# ridicideskaV3.net
KiCad netlist of a schematic drawn in EAGLE
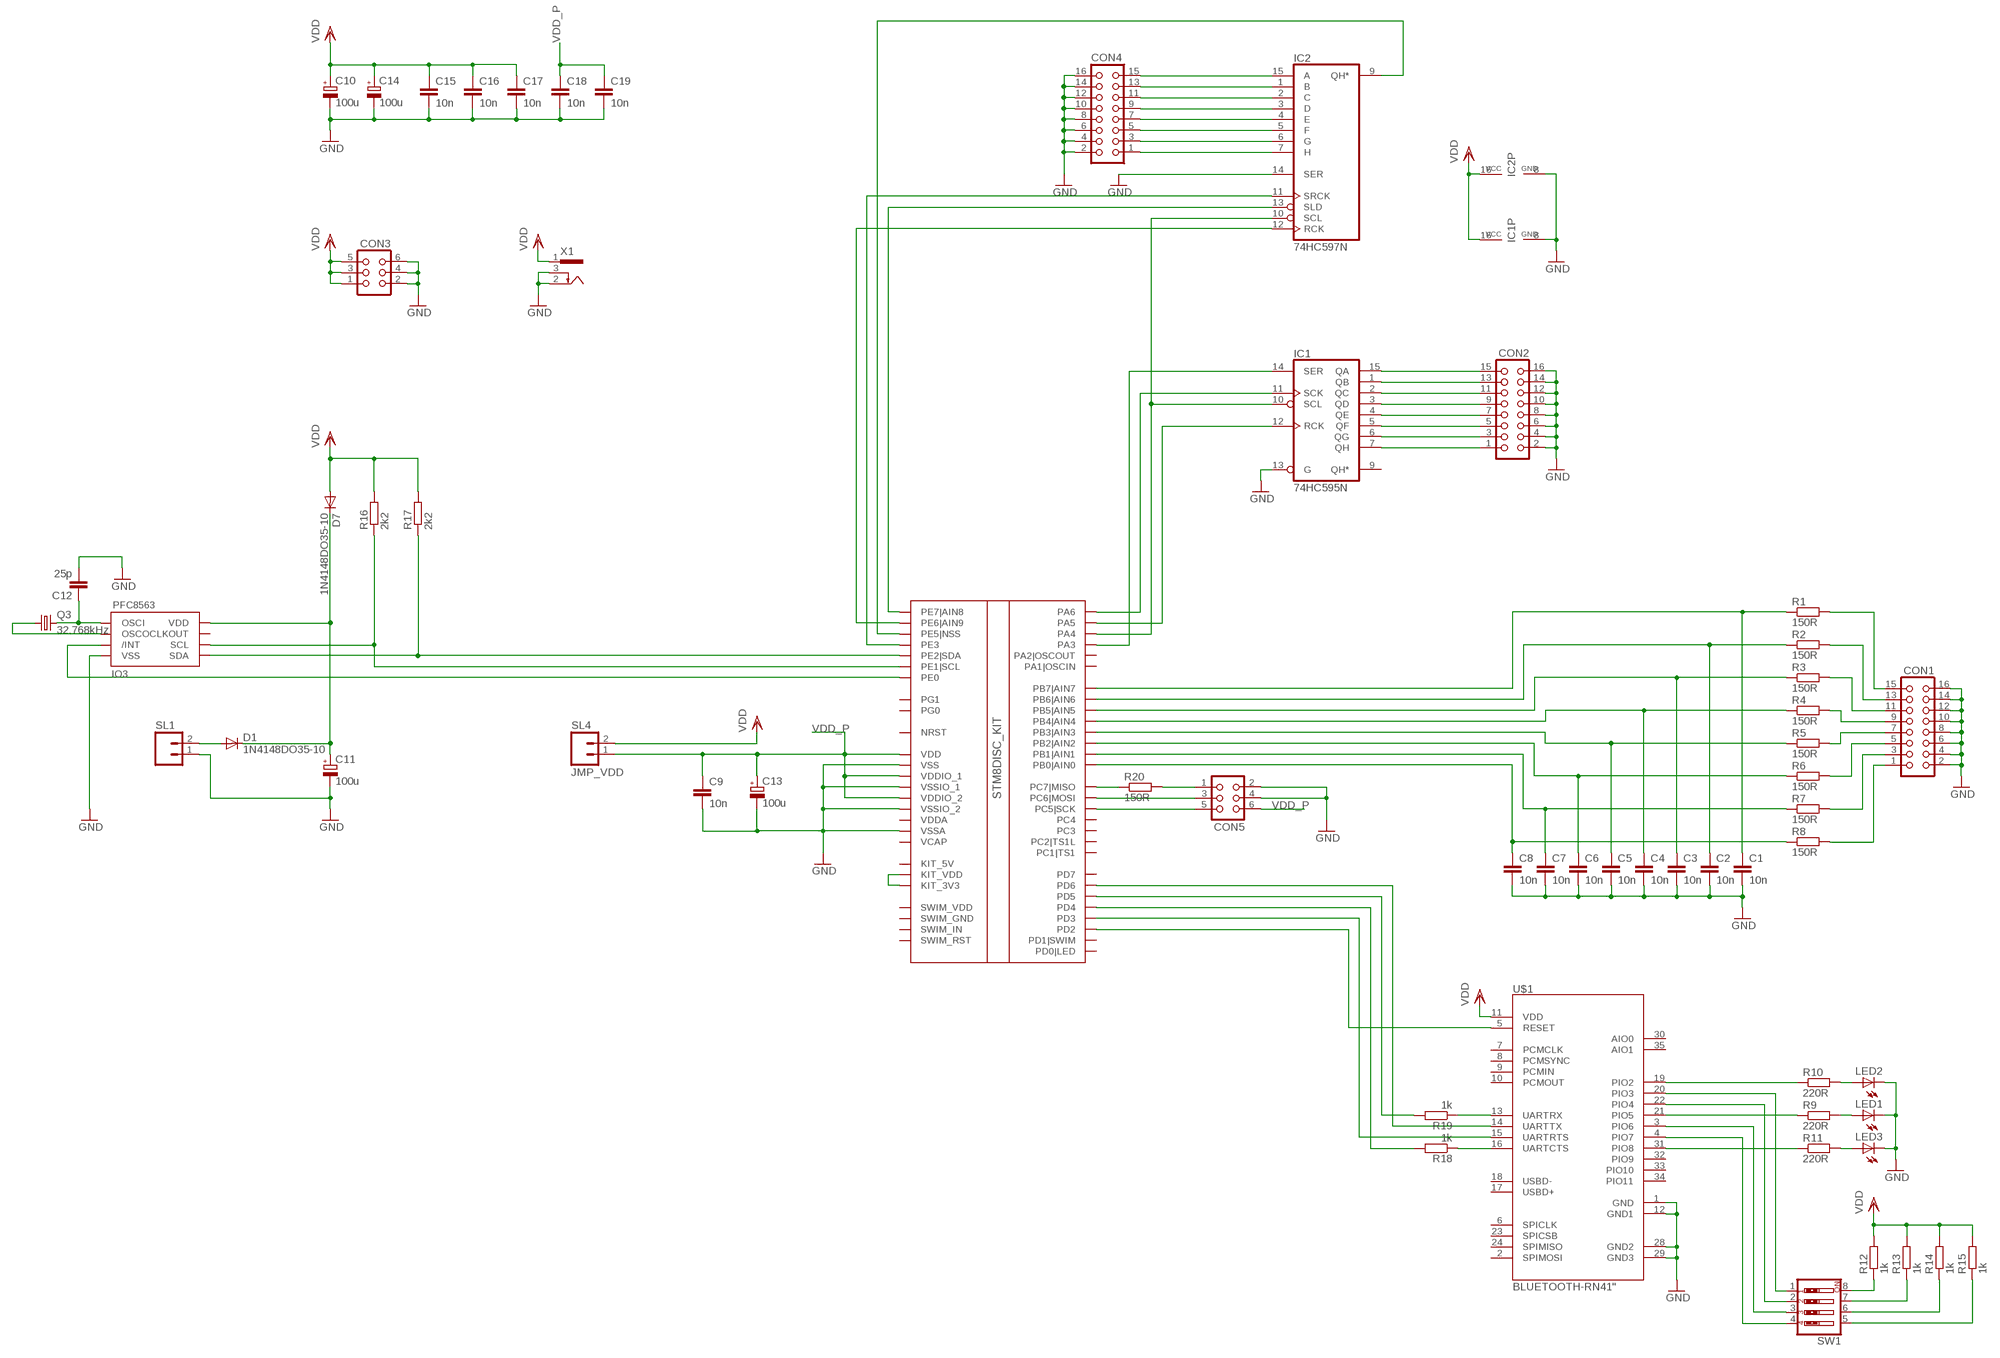
[diagram p0: schematic, sheet 1]

(export (version "E")
  (design (tool "Eeschema 10.0.6"))
  (components
    (comp (ref "C1")
      (value "10n")
      (footprint "eagle-import:C0805")
      (libsource (lib "eagle-import") (part "C-EUC0805"))
    )
    (comp (ref "C2")
      (value "10n")
      (footprint "eagle-import:C0805")
      (libsource (lib "eagle-import") (part "C-EUC0805"))
    )
    (comp (ref "C3")
      (value "10n")
      (footprint "eagle-import:C0805")
      (libsource (lib "eagle-import") (part "C-EUC0805"))
    )
    (comp (ref "C4")
      (value "10n")
      (footprint "eagle-import:C0805")
      (libsource (lib "eagle-import") (part "C-EUC0805"))
    )
    (comp (ref "C5")
      (value "10n")
      (footprint "eagle-import:C0805")
      (libsource (lib "eagle-import") (part "C-EUC0805"))
    )
    (comp (ref "C6")
      (value "10n")
      (footprint "eagle-import:C0805")
      (libsource (lib "eagle-import") (part "C-EUC0805"))
    )
    (comp (ref "C7")
      (value "10n")
      (footprint "eagle-import:C0805")
      (libsource (lib "eagle-import") (part "C-EUC0805"))
    )
    (comp (ref "C8")
      (value "10n")
      (footprint "eagle-import:C0805")
      (libsource (lib "eagle-import") (part "C-EUC0805"))
    )
    (comp (ref "C9")
      (value "10n")
      (footprint "eagle-import:C050-045X075")
      (libsource (lib "eagle-import") (part "C-EU050-045X075"))
    )
    (comp (ref "C10")
      (value "100u")
      (footprint "eagle-import:E5-10,5")
      (libsource (lib "eagle-import") (part "CPOL-EUE5-10.5"))
    )
    (comp (ref "C11")
      (value "100u")
      (footprint "eagle-import:E5-10,5")
      (libsource (lib "eagle-import") (part "CPOL-EUE5-10.5"))
    )
    (comp (ref "C12")
      (value "25p")
      (footprint "eagle-import:C0603")
      (libsource (lib "eagle-import") (part "C-EUC0603"))
    )
    (comp (ref "C13")
      (value "100u")
      (footprint "eagle-import:E5-10,5")
      (libsource (lib "eagle-import") (part "CPOL-EUE5-10.5"))
    )
    (comp (ref "C14")
      (value "100u")
      (footprint "eagle-import:E5-10,5")
      (libsource (lib "eagle-import") (part "CPOL-EUE5-10.5"))
    )
    (comp (ref "C15")
      (value "10n")
      (footprint "eagle-import:C050-045X075")
      (libsource (lib "eagle-import") (part "C-EU050-045X075"))
    )
    (comp (ref "C16")
      (value "10n")
      (footprint "eagle-import:C050-045X075")
      (libsource (lib "eagle-import") (part "C-EU050-045X075"))
    )
    (comp (ref "C17")
      (value "10n")
      (footprint "eagle-import:C0805")
      (libsource (lib "eagle-import") (part "C-EUC0805"))
    )
    (comp (ref "C18")
      (value "10n")
      (footprint "eagle-import:C0805")
      (libsource (lib "eagle-import") (part "C-EUC0805"))
    )
    (comp (ref "C19")
      (value "10n")
      (footprint "eagle-import:C0805")
      (libsource (lib "eagle-import") (part "C-EUC0805"))
    )
    (comp (ref "CON1")
      (value "CON16")
      (footprint "eagle-import:CON16")
      (libsource (lib "eagle-import") (part "CON16"))
    )
    (comp (ref "CON2")
      (value "CON16")
      (footprint "eagle-import:CON16")
      (libsource (lib "eagle-import") (part "CON16"))
    )
    (comp (ref "CON3")
      (value "CON06")
      (footprint "eagle-import:CON06")
      (libsource (lib "eagle-import") (part "CON06"))
    )
    (comp (ref "CON4")
      (value "CON16")
      (footprint "eagle-import:CON16")
      (libsource (lib "eagle-import") (part "CON16"))
    )
    (comp (ref "CON5")
      (value "CON06")
      (footprint "eagle-import:CON06")
      (libsource (lib "eagle-import") (part "CON06"))
    )
    (comp (ref "D1")
      (value "1N4148DO35-10")
      (footprint "eagle-import:DO35-10")
      (libsource (lib "eagle-import") (part "1N4148DO35-10"))
    )
    (comp (ref "D7")
      (value "1N4148DO35-10")
      (footprint "eagle-import:DO35-10")
      (libsource (lib "eagle-import") (part "1N4148DO35-10"))
    )
    (comp (ref "IC1")
      (value "74HC595N")
      (footprint "eagle-import:DIL16")
      (libsource (lib "eagle-import") (part "74595NHC"))
    )
    (comp (ref "IC2")
      (value "74HC597N")
      (footprint "eagle-import:DIL16")
      (libsource (lib "eagle-import") (part "74597NHC"))
    )
    (comp (ref "IO1")
      (value "STM8_KIT")
      (footprint "eagle-import:STM8SDISCOVERY")
      (libsource (lib "eagle-import") (part "STM8_KIT"))
    )
    (comp (ref "IO3")
      (value "PFC8563")
      (footprint "eagle-import:SO08")
      (libsource (lib "eagle-import") (part "PFC8563"))
    )
    (comp (ref "LED1")
      (value "LED3MM")
      (footprint "eagle-import:LED3MM")
      (libsource (lib "eagle-import") (part "LED3MM"))
    )
    (comp (ref "LED2")
      (value "LED3MM")
      (footprint "eagle-import:LED3MM")
      (libsource (lib "eagle-import") (part "LED3MM"))
    )
    (comp (ref "LED3")
      (value "LED3MM")
      (footprint "eagle-import:LED3MM")
      (libsource (lib "eagle-import") (part "LED3MM"))
    )
    (comp (ref "Q3")
      (value "32.768kHz")
      (footprint "eagle-import:TC26V")
      (libsource (lib "eagle-import") (part "CRYSTALTC26V"))
    )
    (comp (ref "R1")
      (value "150R")
      (footprint "eagle-import:0207_12")
      (libsource (lib "eagle-import") (part "R-EU_0207/12"))
    )
    (comp (ref "R2")
      (value "150R")
      (footprint "eagle-import:0207_12")
      (libsource (lib "eagle-import") (part "R-EU_0207/12"))
    )
    (comp (ref "R3")
      (value "150R")
      (footprint "eagle-import:0207_12")
      (libsource (lib "eagle-import") (part "R-EU_0207/12"))
    )
    (comp (ref "R4")
      (value "150R")
      (footprint "eagle-import:0207_12")
      (libsource (lib "eagle-import") (part "R-EU_0207/12"))
    )
    (comp (ref "R5")
      (value "150R")
      (footprint "eagle-import:0207_12")
      (libsource (lib "eagle-import") (part "R-EU_0207/12"))
    )
    (comp (ref "R6")
      (value "150R")
      (footprint "eagle-import:0207_12")
      (libsource (lib "eagle-import") (part "R-EU_0207/12"))
    )
    (comp (ref "R7")
      (value "150R")
      (footprint "eagle-import:0207_12")
      (libsource (lib "eagle-import") (part "R-EU_0207/12"))
    )
    (comp (ref "R8")
      (value "150R")
      (footprint "eagle-import:0207_12")
      (libsource (lib "eagle-import") (part "R-EU_0207/12"))
    )
    (comp (ref "R9")
      (value "220R")
      (footprint "eagle-import:0207_12")
      (libsource (lib "eagle-import") (part "R-EU_0207/12"))
    )
    (comp (ref "R10")
      (value "220R")
      (footprint "eagle-import:0207_12")
      (libsource (lib "eagle-import") (part "R-EU_0207/12"))
    )
    (comp (ref "R11")
      (value "220R")
      (footprint "eagle-import:0207_12")
      (libsource (lib "eagle-import") (part "R-EU_0207/12"))
    )
    (comp (ref "R12")
      (value "1k")
      (footprint "eagle-import:0207_12")
      (libsource (lib "eagle-import") (part "R-EU_0207/12"))
    )
    (comp (ref "R13")
      (value "1k")
      (footprint "eagle-import:0207_12")
      (libsource (lib "eagle-import") (part "R-EU_0207/12"))
    )
    (comp (ref "R14")
      (value "1k")
      (footprint "eagle-import:0207_12")
      (libsource (lib "eagle-import") (part "R-EU_0207/12"))
    )
    (comp (ref "R15")
      (value "1k")
      (footprint "eagle-import:0207_12")
      (libsource (lib "eagle-import") (part "R-EU_0207/12"))
    )
    (comp (ref "R16")
      (value "2k2")
      (footprint "eagle-import:0207_12")
      (libsource (lib "eagle-import") (part "R-EU_0207/12"))
    )
    (comp (ref "R17")
      (value "2k2")
      (footprint "eagle-import:0207_12")
      (libsource (lib "eagle-import") (part "R-EU_0207/12"))
    )
    (comp (ref "R18")
      (value "1k")
      (footprint "eagle-import:0207_12")
      (libsource (lib "eagle-import") (part "R-EU_0207/12"))
    )
    (comp (ref "R19")
      (value "1k")
      (footprint "eagle-import:0207_12")
      (libsource (lib "eagle-import") (part "R-EU_0207/12"))
    )
    (comp (ref "R20")
      (value "150R")
      (footprint "eagle-import:R0805")
      (libsource (lib "eagle-import") (part "R-EU_R0805"))
    )
    (comp (ref "SL1")
      (value "M02")
      (footprint "eagle-import:02P")
      (libsource (lib "eagle-import") (part "M02"))
    )
    (comp (ref "SL4")
      (value "JMP_VDD")
      (footprint "eagle-import:02P")
      (libsource (lib "eagle-import") (part "M02"))
    )
    (comp (ref "SW1")
      (value "SW_DIP-4")
      (footprint "eagle-import:EDG-04")
      (libsource (lib "eagle-import") (part "SW_DIP-4"))
    )
    (comp (ref "U$1")
      (value "BLUETOOTH-RN41\"")
      (footprint "eagle-import:RN41")
      (libsource (lib "eagle-import") (part "BLUETOOTH-RN41{dblquote}"))
    )
    (comp (ref "X1")
      (value "733980-62")
      (footprint "eagle-import:733980-62")
      (libsource (lib "eagle-import") (part "73398?0-62"))
    )
  )
  (nets
    (net (code "1") (name "/VDD_P") (class "Default")
      (node (ref "C13") (pin "+") (pinfunction "+_+") (pintype "passive"))
      (node (ref "C18") (pin "1") (pinfunction "1_1") (pintype "passive"))
      (node (ref "C19") (pin "1") (pinfunction "1_1") (pintype "passive"))
      (node (ref "C9") (pin "1") (pinfunction "1_1") (pintype "passive"))
      (node (ref "CON5") (pin "6") (pinfunction "6_6") (pintype "passive"))
      (node (ref "IO1") (pin "VDD") (pinfunction "VDD_VDD") (pintype "bidirectional"))
      (node (ref "IO1") (pin "VDDIO_1") (pinfunction "VDDIO_1_VDDIO_1") (pintype "bidirectional"))
      (node (ref "IO1") (pin "VDDIO_2") (pinfunction "VDDIO_2_VDDIO_2") (pintype "bidirectional"))
      (node (ref "SL4") (pin "1") (pinfunction "1_1") (pintype "passive"))
    )
    (net (code "2") (name "GND") (class "Default")
      (node (ref "C1") (pin "2") (pinfunction "2_2") (pintype "passive"))
      (node (ref "C10") (pin "-") (pinfunction "-_-") (pintype "passive"))
      (node (ref "C11") (pin "-") (pinfunction "-_-") (pintype "passive"))
      (node (ref "C12") (pin "2") (pinfunction "2_2") (pintype "passive"))
      (node (ref "C13") (pin "-") (pinfunction "-_-") (pintype "passive"))
      (node (ref "C14") (pin "-") (pinfunction "-_-") (pintype "passive"))
      (node (ref "C15") (pin "2") (pinfunction "2_2") (pintype "passive"))
      (node (ref "C16") (pin "2") (pinfunction "2_2") (pintype "passive"))
      (node (ref "C17") (pin "2") (pinfunction "2_2") (pintype "passive"))
      (node (ref "C18") (pin "2") (pinfunction "2_2") (pintype "passive"))
      (node (ref "C19") (pin "2") (pinfunction "2_2") (pintype "passive"))
      (node (ref "C2") (pin "2") (pinfunction "2_2") (pintype "passive"))
      (node (ref "C3") (pin "2") (pinfunction "2_2") (pintype "passive"))
      (node (ref "C4") (pin "2") (pinfunction "2_2") (pintype "passive"))
      (node (ref "C5") (pin "2") (pinfunction "2_2") (pintype "passive"))
      (node (ref "C6") (pin "2") (pinfunction "2_2") (pintype "passive"))
      (node (ref "C7") (pin "2") (pinfunction "2_2") (pintype "passive"))
      (node (ref "C8") (pin "2") (pinfunction "2_2") (pintype "passive"))
      (node (ref "C9") (pin "2") (pinfunction "2_2") (pintype "passive"))
      (node (ref "CON1") (pin "10") (pinfunction "10_10") (pintype "passive"))
      (node (ref "CON1") (pin "12") (pinfunction "12_12") (pintype "passive"))
      (node (ref "CON1") (pin "14") (pinfunction "14_14") (pintype "passive"))
      (node (ref "CON1") (pin "16") (pinfunction "16_16") (pintype "passive"))
      (node (ref "CON1") (pin "2") (pinfunction "2_2") (pintype "passive"))
      (node (ref "CON1") (pin "4") (pinfunction "4_4") (pintype "passive"))
      (node (ref "CON1") (pin "6") (pinfunction "6_6") (pintype "passive"))
      (node (ref "CON1") (pin "8") (pinfunction "8_8") (pintype "passive"))
      (node (ref "CON2") (pin "10") (pinfunction "10_10") (pintype "passive"))
      (node (ref "CON2") (pin "12") (pinfunction "12_12") (pintype "passive"))
      (node (ref "CON2") (pin "14") (pinfunction "14_14") (pintype "passive"))
      (node (ref "CON2") (pin "16") (pinfunction "16_16") (pintype "passive"))
      (node (ref "CON2") (pin "2") (pinfunction "2_2") (pintype "passive"))
      (node (ref "CON2") (pin "4") (pinfunction "4_4") (pintype "passive"))
      (node (ref "CON2") (pin "6") (pinfunction "6_6") (pintype "passive"))
      (node (ref "CON2") (pin "8") (pinfunction "8_8") (pintype "passive"))
      (node (ref "CON3") (pin "2") (pinfunction "2_2") (pintype "passive"))
      (node (ref "CON3") (pin "4") (pinfunction "4_4") (pintype "passive"))
      (node (ref "CON3") (pin "6") (pinfunction "6_6") (pintype "passive"))
      (node (ref "CON4") (pin "10") (pinfunction "10_10") (pintype "passive"))
      (node (ref "CON4") (pin "12") (pinfunction "12_12") (pintype "passive"))
      (node (ref "CON4") (pin "14") (pinfunction "14_14") (pintype "passive"))
      (node (ref "CON4") (pin "16") (pinfunction "16_16") (pintype "passive"))
      (node (ref "CON4") (pin "2") (pinfunction "2_2") (pintype "passive"))
      (node (ref "CON4") (pin "4") (pinfunction "4_4") (pintype "passive"))
      (node (ref "CON4") (pin "6") (pinfunction "6_6") (pintype "passive"))
      (node (ref "CON4") (pin "8") (pinfunction "8_8") (pintype "passive"))
      (node (ref "CON5") (pin "2") (pinfunction "2_2") (pintype "passive"))
      (node (ref "CON5") (pin "4") (pinfunction "4_4") (pintype "passive"))
      (node (ref "IC1") (pin "13") (pinfunction "G_13") (pintype "input"))
      (node (ref "IC1") (pin "8") (pinfunction "GND_8") (pintype "power_in"))
      (node (ref "IC2") (pin "14") (pinfunction "SER_14") (pintype "input"))
      (node (ref "IC2") (pin "8") (pinfunction "GND_8") (pintype "power_in"))
      (node (ref "IO1") (pin "VSS") (pinfunction "VSS_VSS") (pintype "bidirectional"))
      (node (ref "IO1") (pin "VSSA") (pinfunction "VSSA_VSSA") (pintype "bidirectional"))
      (node (ref "IO1") (pin "VSSIO_1") (pinfunction "VSSIO_1_VSSIO_1") (pintype "bidirectional"))
      (node (ref "IO1") (pin "VSSIO_2") (pinfunction "VSSIO_2_VSSIO_2") (pintype "bidirectional"))
      (node (ref "IO3") (pin "4") (pinfunction "VSS_4") (pintype "bidirectional"))
      (node (ref "LED1") (pin "K") (pinfunction "C_K") (pintype "passive"))
      (node (ref "LED2") (pin "K") (pinfunction "C_K") (pintype "passive"))
      (node (ref "LED3") (pin "K") (pinfunction "C_K") (pintype "passive"))
      (node (ref "SL1") (pin "1") (pinfunction "1_1") (pintype "passive"))
      (node (ref "U$1") (pin "1") (pinfunction "GND_1") (pintype "bidirectional"))
      (node (ref "U$1") (pin "12") (pinfunction "GND1_12") (pintype "bidirectional"))
      (node (ref "U$1") (pin "28") (pinfunction "GND2_28") (pintype "bidirectional"))
      (node (ref "U$1") (pin "29") (pinfunction "GND3_29") (pintype "bidirectional"))
      (node (ref "X1") (pin "2") (pinfunction "2_2") (pintype "passive"))
      (node (ref "X1") (pin "3") (pinfunction "3_3") (pintype "passive"))
    )
    (net (code "3") (name "Net-(CON1-Pad1)") (class "Default")
      (node (ref "CON1") (pin "1") (pinfunction "1_1") (pintype "passive"))
      (node (ref "R8") (pin "2") (pinfunction "2_2") (pintype "passive"))
    )
    (net (code "4") (name "Net-(CON1-Pad3)") (class "Default")
      (node (ref "CON1") (pin "3") (pinfunction "3_3") (pintype "passive"))
      (node (ref "R7") (pin "2") (pinfunction "2_2") (pintype "passive"))
    )
    (net (code "5") (name "Net-(CON1-Pad5)") (class "Default")
      (node (ref "CON1") (pin "5") (pinfunction "5_5") (pintype "passive"))
      (node (ref "R6") (pin "2") (pinfunction "2_2") (pintype "passive"))
    )
    (net (code "6") (name "Net-(CON1-Pad7)") (class "Default")
      (node (ref "CON1") (pin "7") (pinfunction "7_7") (pintype "passive"))
      (node (ref "R5") (pin "2") (pinfunction "2_2") (pintype "passive"))
    )
    (net (code "7") (name "Net-(CON1-Pad9)") (class "Default")
      (node (ref "CON1") (pin "9") (pinfunction "9_9") (pintype "passive"))
      (node (ref "R4") (pin "2") (pinfunction "2_2") (pintype "passive"))
    )
    (net (code "8") (name "Net-(CON1-Pad11)") (class "Default")
      (node (ref "CON1") (pin "11") (pinfunction "11_11") (pintype "passive"))
      (node (ref "R3") (pin "2") (pinfunction "2_2") (pintype "passive"))
    )
    (net (code "9") (name "Net-(CON1-Pad13)") (class "Default")
      (node (ref "CON1") (pin "13") (pinfunction "13_13") (pintype "passive"))
      (node (ref "R2") (pin "2") (pinfunction "2_2") (pintype "passive"))
    )
    (net (code "10") (name "Net-(CON1-Pad15)") (class "Default")
      (node (ref "CON1") (pin "15") (pinfunction "15_15") (pintype "passive"))
      (node (ref "R1") (pin "2") (pinfunction "2_2") (pintype "passive"))
    )
    (net (code "11") (name "Net-(CON5-Pad1)") (class "Default")
      (node (ref "CON5") (pin "1") (pinfunction "1_1") (pintype "passive"))
      (node (ref "R20") (pin "2") (pinfunction "2_2") (pintype "passive"))
    )
    (net (code "12") (name "Net-(D1-PadA)") (class "Default")
      (node (ref "D1") (pin "A") (pinfunction "A_A") (pintype "passive"))
      (node (ref "SL1") (pin "2") (pinfunction "2_2") (pintype "passive"))
    )
    (net (code "13") (name "Net-(IC1A-QA)") (class "Default")
      (node (ref "CON2") (pin "15") (pinfunction "15_15") (pintype "passive"))
      (node (ref "IC1") (pin "15") (pinfunction "QA_15") (pintype "tri_state"))
    )
    (net (code "14") (name "Net-(IC1A-QB)") (class "Default")
      (node (ref "CON2") (pin "13") (pinfunction "13_13") (pintype "passive"))
      (node (ref "IC1") (pin "1") (pinfunction "QB_1") (pintype "tri_state"))
    )
    (net (code "15") (name "Net-(IC1A-QC)") (class "Default")
      (node (ref "CON2") (pin "11") (pinfunction "11_11") (pintype "passive"))
      (node (ref "IC1") (pin "2") (pinfunction "QC_2") (pintype "tri_state"))
    )
    (net (code "16") (name "Net-(IC1A-QD)") (class "Default")
      (node (ref "CON2") (pin "9") (pinfunction "9_9") (pintype "passive"))
      (node (ref "IC1") (pin "3") (pinfunction "QD_3") (pintype "tri_state"))
    )
    (net (code "17") (name "Net-(IC1A-QE)") (class "Default")
      (node (ref "CON2") (pin "7") (pinfunction "7_7") (pintype "passive"))
      (node (ref "IC1") (pin "4") (pinfunction "QE_4") (pintype "tri_state"))
    )
    (net (code "18") (name "Net-(IC1A-QF)") (class "Default")
      (node (ref "CON2") (pin "5") (pinfunction "5_5") (pintype "passive"))
      (node (ref "IC1") (pin "5") (pinfunction "QF_5") (pintype "tri_state"))
    )
    (net (code "19") (name "Net-(IC1A-QG)") (class "Default")
      (node (ref "CON2") (pin "3") (pinfunction "3_3") (pintype "passive"))
      (node (ref "IC1") (pin "6") (pinfunction "QG_6") (pintype "tri_state"))
    )
    (net (code "20") (name "Net-(IC1A-QH)") (class "Default")
      (node (ref "CON2") (pin "1") (pinfunction "1_1") (pintype "passive"))
      (node (ref "IC1") (pin "7") (pinfunction "QH_7") (pintype "tri_state"))
    )
    (net (code "21") (name "Net-(IC1A-RCK)") (class "Default")
      (node (ref "IC1") (pin "12") (pinfunction "RCK_12") (pintype "input"))
      (node (ref "IO1") (pin "PA5") (pinfunction "PA5_PA5") (pintype "bidirectional"))
    )
    (net (code "22") (name "Net-(IC1A-SCK)") (class "Default")
      (node (ref "IC1") (pin "11") (pinfunction "SCK_11") (pintype "input"))
      (node (ref "IO1") (pin "PA6") (pinfunction "PA6_PA6") (pintype "bidirectional"))
    )
    (net (code "23") (name "Net-(IC1A-SCL)") (class "Default")
      (node (ref "IC1") (pin "10") (pinfunction "SCL_10") (pintype "input"))
      (node (ref "IC2") (pin "10") (pinfunction "SCL_10") (pintype "input"))
      (node (ref "IO1") (pin "PA4") (pinfunction "PA4_PA4") (pintype "bidirectional"))
    )
    (net (code "24") (name "Net-(IC1A-SER)") (class "Default")
      (node (ref "IC1") (pin "14") (pinfunction "SER_14") (pintype "input"))
      (node (ref "IO1") (pin "PA3") (pinfunction "PA3_PA3") (pintype "bidirectional"))
    )
    (net (code "25") (name "Net-(IC2A-A)") (class "Default")
      (node (ref "CON4") (pin "15") (pinfunction "15_15") (pintype "passive"))
      (node (ref "IC2") (pin "15") (pinfunction "A_15") (pintype "input"))
    )
    (net (code "26") (name "Net-(IC2A-B)") (class "Default")
      (node (ref "CON4") (pin "13") (pinfunction "13_13") (pintype "passive"))
      (node (ref "IC2") (pin "1") (pinfunction "B_1") (pintype "input"))
    )
    (net (code "27") (name "Net-(IC2A-C)") (class "Default")
      (node (ref "CON4") (pin "11") (pinfunction "11_11") (pintype "passive"))
      (node (ref "IC2") (pin "2") (pinfunction "C_2") (pintype "input"))
    )
    (net (code "28") (name "Net-(IC2A-D)") (class "Default")
      (node (ref "CON4") (pin "9") (pinfunction "9_9") (pintype "passive"))
      (node (ref "IC2") (pin "3") (pinfunction "D_3") (pintype "input"))
    )
    (net (code "29") (name "Net-(IC2A-E)") (class "Default")
      (node (ref "CON4") (pin "7") (pinfunction "7_7") (pintype "passive"))
      (node (ref "IC2") (pin "4") (pinfunction "E_4") (pintype "input"))
    )
    (net (code "30") (name "Net-(IC2A-F)") (class "Default")
      (node (ref "CON4") (pin "5") (pinfunction "5_5") (pintype "passive"))
      (node (ref "IC2") (pin "5") (pinfunction "F_5") (pintype "input"))
    )
    (net (code "31") (name "Net-(IC2A-G)") (class "Default")
      (node (ref "CON4") (pin "3") (pinfunction "3_3") (pintype "passive"))
      (node (ref "IC2") (pin "6") (pinfunction "G_6") (pintype "input"))
    )
    (net (code "32") (name "Net-(IC2A-H)") (class "Default")
      (node (ref "CON4") (pin "1") (pinfunction "1_1") (pintype "passive"))
      (node (ref "IC2") (pin "7") (pinfunction "H_7") (pintype "input"))
    )
    (net (code "33") (name "Net-(IC2A-QH*)") (class "Default")
      (node (ref "IC2") (pin "9") (pinfunction "QH*_9") (pintype "output"))
      (node (ref "IO1") (pin "PE5") (pinfunction "PE5|NSS_PE5") (pintype "bidirectional"))
    )
    (net (code "34") (name "Net-(IC2A-RCK)") (class "Default")
      (node (ref "IC2") (pin "12") (pinfunction "RCK_12") (pintype "input"))
      (node (ref "IO1") (pin "PE6") (pinfunction "PE6|AIN9_PE6") (pintype "bidirectional"))
    )
    (net (code "35") (name "Net-(IC2A-SLD)") (class "Default")
      (node (ref "IC2") (pin "13") (pinfunction "SLD_13") (pintype "input"))
      (node (ref "IO1") (pin "PE7") (pinfunction "PE7|AIN8_PE7") (pintype "bidirectional"))
    )
    (net (code "36") (name "Net-(IC2A-SRCK)") (class "Default")
      (node (ref "IC2") (pin "11") (pinfunction "SRCK_11") (pintype "input"))
      (node (ref "IO1") (pin "PE3") (pinfunction "PE3_PE3") (pintype "bidirectional"))
    )
    (net (code "37") (name "Net-(IO1-PB0|AIN0)") (class "Default")
      (node (ref "C8") (pin "1") (pinfunction "1_1") (pintype "passive"))
      (node (ref "IO1") (pin "PB0") (pinfunction "PB0|AIN0_PB0") (pintype "bidirectional"))
      (node (ref "R8") (pin "1") (pinfunction "1_1") (pintype "passive"))
    )
    (net (code "38") (name "Net-(IO1-PB1|AIN1)") (class "Default")
      (node (ref "C7") (pin "1") (pinfunction "1_1") (pintype "passive"))
      (node (ref "IO1") (pin "PB1") (pinfunction "PB1|AIN1_PB1") (pintype "bidirectional"))
      (node (ref "R7") (pin "1") (pinfunction "1_1") (pintype "passive"))
    )
    (net (code "39") (name "Net-(IO1-PB2|AIN2)") (class "Default")
      (node (ref "C6") (pin "1") (pinfunction "1_1") (pintype "passive"))
      (node (ref "IO1") (pin "PB2") (pinfunction "PB2|AIN2_PB2") (pintype "bidirectional"))
      (node (ref "R6") (pin "1") (pinfunction "1_1") (pintype "passive"))
    )
    (net (code "40") (name "Net-(IO1-PB3|AIN3)") (class "Default")
      (node (ref "C5") (pin "1") (pinfunction "1_1") (pintype "passive"))
      (node (ref "IO1") (pin "PB3") (pinfunction "PB3|AIN3_PB3") (pintype "bidirectional"))
      (node (ref "R5") (pin "1") (pinfunction "1_1") (pintype "passive"))
    )
    (net (code "41") (name "Net-(IO1-PB4|AIN4)") (class "Default")
      (node (ref "C4") (pin "1") (pinfunction "1_1") (pintype "passive"))
      (node (ref "IO1") (pin "PB4") (pinfunction "PB4|AIN4_PB4") (pintype "bidirectional"))
      (node (ref "R4") (pin "1") (pinfunction "1_1") (pintype "passive"))
    )
    (net (code "42") (name "Net-(IO1-PB5|AIN5)") (class "Default")
      (node (ref "C3") (pin "1") (pinfunction "1_1") (pintype "passive"))
      (node (ref "IO1") (pin "PB5") (pinfunction "PB5|AIN5_PB5") (pintype "bidirectional"))
      (node (ref "R3") (pin "1") (pinfunction "1_1") (pintype "passive"))
    )
    (net (code "43") (name "Net-(IO1-PB6|AIN6)") (class "Default")
      (node (ref "C2") (pin "1") (pinfunction "1_1") (pintype "passive"))
      (node (ref "IO1") (pin "PB6") (pinfunction "PB6|AIN6_PB6") (pintype "bidirectional"))
      (node (ref "R2") (pin "1") (pinfunction "1_1") (pintype "passive"))
    )
    (net (code "44") (name "Net-(IO1-PB7|AIN7)") (class "Default")
      (node (ref "C1") (pin "1") (pinfunction "1_1") (pintype "passive"))
      (node (ref "IO1") (pin "PB7") (pinfunction "PB7|AIN7_PB7") (pintype "bidirectional"))
      (node (ref "R1") (pin "1") (pinfunction "1_1") (pintype "passive"))
    )
    (net (code "45") (name "Net-(IO1-PC5|SCK)") (class "Default")
      (node (ref "CON5") (pin "5") (pinfunction "5_5") (pintype "passive"))
      (node (ref "IO1") (pin "PC5") (pinfunction "PC5|SCK_PC5") (pintype "bidirectional"))
    )
    (net (code "46") (name "Net-(IO1-PC6|MOSI)") (class "Default")
      (node (ref "CON5") (pin "3") (pinfunction "3_3") (pintype "passive"))
      (node (ref "IO1") (pin "PC6") (pinfunction "PC6|MOSI_PC6") (pintype "bidirectional"))
    )
    (net (code "47") (name "Net-(IO1-PC7|MISO)") (class "Default")
      (node (ref "IO1") (pin "PC7") (pinfunction "PC7|MISO_PC7") (pintype "bidirectional"))
      (node (ref "R20") (pin "1") (pinfunction "1_1") (pintype "passive"))
    )
    (net (code "48") (name "Net-(IO1-PE1|SCL)") (class "Default")
      (node (ref "IO1") (pin "PE1") (pinfunction "PE1|SCL_PE1") (pintype "bidirectional"))
      (node (ref "IO3") (pin "6") (pinfunction "SCL_6") (pintype "bidirectional"))
      (node (ref "R16") (pin "1") (pinfunction "1_1") (pintype "passive"))
    )
    (net (code "49") (name "Net-(IO1-PE2|SDA)") (class "Default")
      (node (ref "IO1") (pin "PE2") (pinfunction "PE2|SDA_PE2") (pintype "bidirectional"))
      (node (ref "IO3") (pin "5") (pinfunction "SDA_5") (pintype "bidirectional"))
      (node (ref "R17") (pin "1") (pinfunction "1_1") (pintype "passive"))
    )
    (net (code "50") (name "Net-(IO1-PadKIT_3V3)") (class "Default")
      (node (ref "IO1") (pin "KIT_3V3") (pinfunction "KIT_3V3_KIT_3V3") (pintype "bidirectional"))
      (node (ref "IO1") (pin "KIT_VDD") (pinfunction "KIT_VDD_KIT_VDD") (pintype "bidirectional"))
    )
    (net (code "51") (name "Net-(IO1-PadPD4)") (class "Default")
      (node (ref "IO1") (pin "PD4") (pinfunction "PD4_PD4") (pintype "bidirectional"))
      (node (ref "R18") (pin "2") (pinfunction "2_2") (pintype "passive"))
    )
    (net (code "52") (name "Net-(IO1-PadPD5)") (class "Default")
      (node (ref "IO1") (pin "PD5") (pinfunction "PD5_PD5") (pintype "bidirectional"))
      (node (ref "R19") (pin "2") (pinfunction "2_2") (pintype "passive"))
    )
    (net (code "53") (name "Net-(IO3-OSCI)") (class "Default")
      (node (ref "C12") (pin "1") (pinfunction "1_1") (pintype "passive"))
      (node (ref "IO3") (pin "1") (pinfunction "OSCI_1") (pintype "bidirectional"))
      (node (ref "Q3") (pin "2") (pinfunction "2_2") (pintype "passive"))
    )
    (net (code "54") (name "Net-(IO3-OSCO)") (class "Default")
      (node (ref "IO3") (pin "2") (pinfunction "OSCO_2") (pintype "bidirectional"))
      (node (ref "Q3") (pin "1") (pinfunction "1_1") (pintype "passive"))
    )
    (net (code "55") (name "Net-(IO3-VDD)") (class "Default")
      (node (ref "C11") (pin "+") (pinfunction "+_+") (pintype "passive"))
      (node (ref "D1") (pin "C") (pinfunction "C_C") (pintype "passive"))
      (node (ref "D7") (pin "C") (pinfunction "C_C") (pintype "passive"))
      (node (ref "IO3") (pin "8") (pinfunction "VDD_8") (pintype "bidirectional"))
    )
    (net (code "56") (name "Net-(IO3-{slash}INT)") (class "Default")
      (node (ref "IO1") (pin "PE0") (pinfunction "PE0_PE0") (pintype "bidirectional"))
      (node (ref "IO3") (pin "3") (pinfunction "/INT_3") (pintype "bidirectional"))
    )
    (net (code "57") (name "Net-(LED1-PadA)") (class "Default")
      (node (ref "LED1") (pin "A") (pinfunction "A_A") (pintype "passive"))
      (node (ref "R9") (pin "2") (pinfunction "2_2") (pintype "passive"))
    )
    (net (code "58") (name "Net-(LED2-PadA)") (class "Default")
      (node (ref "LED2") (pin "A") (pinfunction "A_A") (pintype "passive"))
      (node (ref "R10") (pin "2") (pinfunction "2_2") (pintype "passive"))
    )
    (net (code "59") (name "Net-(LED3-PadA)") (class "Default")
      (node (ref "LED3") (pin "A") (pinfunction "A_A") (pintype "passive"))
      (node (ref "R11") (pin "2") (pinfunction "2_2") (pintype "passive"))
    )
    (net (code "60") (name "Net-(R12-Pad1)") (class "Default")
      (node (ref "R12") (pin "1") (pinfunction "1_1") (pintype "passive"))
      (node (ref "SW1") (pin "8") (pinfunction "8_8") (pintype "passive"))
    )
    (net (code "61") (name "Net-(R13-Pad1)") (class "Default")
      (node (ref "R13") (pin "1") (pinfunction "1_1") (pintype "passive"))
      (node (ref "SW1") (pin "7") (pinfunction "7_7") (pintype "passive"))
    )
    (net (code "62") (name "Net-(R14-Pad1)") (class "Default")
      (node (ref "R14") (pin "1") (pinfunction "1_1") (pintype "passive"))
      (node (ref "SW1") (pin "6") (pinfunction "6_6") (pintype "passive"))
    )
    (net (code "63") (name "Net-(R15-Pad1)") (class "Default")
      (node (ref "R15") (pin "1") (pinfunction "1_1") (pintype "passive"))
      (node (ref "SW1") (pin "5") (pinfunction "5_5") (pintype "passive"))
    )
    (net (code "64") (name "Net-(U$1-PIO2)") (class "Default")
      (node (ref "R10") (pin "1") (pinfunction "1_1") (pintype "passive"))
      (node (ref "U$1") (pin "19") (pinfunction "PIO2_19") (pintype "bidirectional"))
    )
    (net (code "65") (name "Net-(U$1-PIO3)") (class "Default")
      (node (ref "SW1") (pin "1") (pinfunction "1_1") (pintype "passive"))
      (node (ref "U$1") (pin "20") (pinfunction "PIO3_20") (pintype "bidirectional"))
    )
    (net (code "66") (name "Net-(U$1-PIO4)") (class "Default")
      (node (ref "SW1") (pin "2") (pinfunction "2_2") (pintype "passive"))
      (node (ref "U$1") (pin "22") (pinfunction "PIO4_22") (pintype "bidirectional"))
    )
    (net (code "67") (name "Net-(U$1-PIO5)") (class "Default")
      (node (ref "R9") (pin "1") (pinfunction "1_1") (pintype "passive"))
      (node (ref "U$1") (pin "21") (pinfunction "PIO5_21") (pintype "bidirectional"))
    )
    (net (code "68") (name "Net-(U$1-PIO6)") (class "Default")
      (node (ref "SW1") (pin "3") (pinfunction "3_3") (pintype "passive"))
      (node (ref "U$1") (pin "3") (pinfunction "PIO6_3") (pintype "bidirectional"))
    )
    (net (code "69") (name "Net-(U$1-PIO7)") (class "Default")
      (node (ref "SW1") (pin "4") (pinfunction "4_4") (pintype "passive"))
      (node (ref "U$1") (pin "4") (pinfunction "PIO7_4") (pintype "bidirectional"))
    )
    (net (code "70") (name "Net-(U$1-PIO8)") (class "Default")
      (node (ref "R11") (pin "1") (pinfunction "1_1") (pintype "passive"))
      (node (ref "U$1") (pin "31") (pinfunction "PIO8_31") (pintype "bidirectional"))
    )
    (net (code "71") (name "Net-(U$1-RESET)") (class "Default")
      (node (ref "IO1") (pin "PD2") (pinfunction "PD2_PD2") (pintype "bidirectional"))
      (node (ref "U$1") (pin "5") (pinfunction "RESET_5") (pintype "bidirectional"))
    )
    (net (code "72") (name "Net-(U$1-UARTCTS)") (class "Default")
      (node (ref "R18") (pin "1") (pinfunction "1_1") (pintype "passive"))
      (node (ref "U$1") (pin "16") (pinfunction "UARTCTS_16") (pintype "bidirectional"))
    )
    (net (code "73") (name "Net-(U$1-UARTRTS)") (class "Default")
      (node (ref "IO1") (pin "PD3") (pinfunction "PD3_PD3") (pintype "bidirectional"))
      (node (ref "U$1") (pin "15") (pinfunction "UARTRTS_15") (pintype "bidirectional"))
    )
    (net (code "74") (name "Net-(U$1-UARTRX)") (class "Default")
      (node (ref "R19") (pin "1") (pinfunction "1_1") (pintype "passive"))
      (node (ref "U$1") (pin "13") (pinfunction "UARTRX_13") (pintype "bidirectional"))
    )
    (net (code "75") (name "Net-(U$1-UARTTX)") (class "Default")
      (node (ref "IO1") (pin "PD6") (pinfunction "PD6_PD6") (pintype "bidirectional"))
      (node (ref "U$1") (pin "14") (pinfunction "UARTTX_14") (pintype "bidirectional"))
    )
    (net (code "76") (name "VDD") (class "Default")
      (node (ref "C10") (pin "+") (pinfunction "+_+") (pintype "passive"))
      (node (ref "C14") (pin "+") (pinfunction "+_+") (pintype "passive"))
      (node (ref "C15") (pin "1") (pinfunction "1_1") (pintype "passive"))
      (node (ref "C16") (pin "1") (pinfunction "1_1") (pintype "passive"))
      (node (ref "C17") (pin "1") (pinfunction "1_1") (pintype "passive"))
      (node (ref "CON3") (pin "1") (pinfunction "1_1") (pintype "passive"))
      (node (ref "CON3") (pin "3") (pinfunction "3_3") (pintype "passive"))
      (node (ref "CON3") (pin "5") (pinfunction "5_5") (pintype "passive"))
      (node (ref "D7") (pin "A") (pinfunction "A_A") (pintype "passive"))
      (node (ref "IC1") (pin "16") (pinfunction "VCC_16") (pintype "power_in"))
      (node (ref "IC2") (pin "16") (pinfunction "VCC_16") (pintype "power_in"))
      (node (ref "R12") (pin "2") (pinfunction "2_2") (pintype "passive"))
      (node (ref "R13") (pin "2") (pinfunction "2_2") (pintype "passive"))
      (node (ref "R14") (pin "2") (pinfunction "2_2") (pintype "passive"))
      (node (ref "R15") (pin "2") (pinfunction "2_2") (pintype "passive"))
      (node (ref "R16") (pin "2") (pinfunction "2_2") (pintype "passive"))
      (node (ref "R17") (pin "2") (pinfunction "2_2") (pintype "passive"))
      (node (ref "SL4") (pin "2") (pinfunction "2_2") (pintype "passive"))
      (node (ref "U$1") (pin "11") (pinfunction "VDD_11") (pintype "bidirectional"))
      (node (ref "X1") (pin "1") (pinfunction "1_1") (pintype "passive"))
    )
    (net (code "77") (name "unconnected-(IC1A-QH*-Pad9)") (class "Default")
      (node (ref "IC1") (pin "9") (pinfunction "QH*_9") (pintype "tri_state"))
    )
    (net (code "78") (name "unconnected-(IO1-PA1|OSCIN-PadPA1)") (class "Default")
      (node (ref "IO1") (pin "PA1") (pinfunction "PA1|OSCIN_PA1") (pintype "bidirectional"))
    )
    (net (code "79") (name "unconnected-(IO1-PA2|OSCOUT-PadPA2)") (class "Default")
      (node (ref "IO1") (pin "PA2") (pinfunction "PA2|OSCOUT_PA2") (pintype "bidirectional"))
    )
    (net (code "80") (name "unconnected-(IO1-PC1|TS1-PadPC1)") (class "Default")
      (node (ref "IO1") (pin "PC1") (pinfunction "PC1|TS1_PC1") (pintype "bidirectional"))
    )
    (net (code "81") (name "unconnected-(IO1-PC2|TS1L-PadPC2)") (class "Default")
      (node (ref "IO1") (pin "PC2") (pinfunction "PC2|TS1L_PC2") (pintype "bidirectional"))
    )
    (net (code "82") (name "unconnected-(IO1-PD0|LED-PadPD0)") (class "Default")
      (node (ref "IO1") (pin "PD0") (pinfunction "PD0|LED_PD0") (pintype "bidirectional"))
    )
    (net (code "83") (name "unconnected-(IO1-PD1|SWIM-PadPD1)") (class "Default")
      (node (ref "IO1") (pin "PD1") (pinfunction "PD1|SWIM_PD1") (pintype "bidirectional"))
    )
    (net (code "84") (name "unconnected-(IO1-PadKIT_5V)") (class "Default")
      (node (ref "IO1") (pin "KIT_5V") (pinfunction "KIT_5V_KIT_5V") (pintype "bidirectional"))
    )
    (net (code "85") (name "unconnected-(IO1-PadNRST)") (class "Default")
      (node (ref "IO1") (pin "NRST") (pinfunction "NRST_NRST") (pintype "bidirectional"))
    )
    (net (code "86") (name "unconnected-(IO1-PadPC3)") (class "Default")
      (node (ref "IO1") (pin "PC3") (pinfunction "PC3_PC3") (pintype "bidirectional"))
    )
    (net (code "87") (name "unconnected-(IO1-PadPC4)") (class "Default")
      (node (ref "IO1") (pin "PC4") (pinfunction "PC4_PC4") (pintype "bidirectional"))
    )
    (net (code "88") (name "unconnected-(IO1-PadPD7)") (class "Default")
      (node (ref "IO1") (pin "PD7") (pinfunction "PD7_PD7") (pintype "bidirectional"))
    )
    (net (code "89") (name "unconnected-(IO1-PadPG0)") (class "Default")
      (node (ref "IO1") (pin "PG0") (pinfunction "PG0_PG0") (pintype "bidirectional"))
    )
    (net (code "90") (name "unconnected-(IO1-PadPG1)") (class "Default")
      (node (ref "IO1") (pin "PG1") (pinfunction "PG1_PG1") (pintype "bidirectional"))
    )
    (net (code "91") (name "unconnected-(IO1-PadSWIM_GND)") (class "Default")
      (node (ref "IO1") (pin "SWIM_GND") (pinfunction "SWIM_GND_SWIM_GND") (pintype "bidirectional"))
    )
    (net (code "92") (name "unconnected-(IO1-PadSWIM_IN)") (class "Default")
      (node (ref "IO1") (pin "SWIM_IN") (pinfunction "SWIM_IN_SWIM_IN") (pintype "bidirectional"))
    )
    (net (code "93") (name "unconnected-(IO1-PadSWIM_RST)") (class "Default")
      (node (ref "IO1") (pin "SWIM_RST") (pinfunction "SWIM_RST_SWIM_RST") (pintype "bidirectional"))
    )
    (net (code "94") (name "unconnected-(IO1-PadSWIM_VDD)") (class "Default")
      (node (ref "IO1") (pin "SWIM_VDD") (pinfunction "SWIM_VDD_SWIM_VDD") (pintype "bidirectional"))
    )
    (net (code "95") (name "unconnected-(IO1-PadVCAP)") (class "Default")
      (node (ref "IO1") (pin "VCAP") (pinfunction "VCAP_VCAP") (pintype "bidirectional"))
    )
    (net (code "96") (name "unconnected-(IO1-PadVDDA)") (class "Default")
      (node (ref "IO1") (pin "VDDA") (pinfunction "VDDA_VDDA") (pintype "bidirectional"))
    )
    (net (code "97") (name "unconnected-(IO3-CLKOUT-Pad7)") (class "Default")
      (node (ref "IO3") (pin "7") (pinfunction "CLKOUT_7") (pintype "bidirectional"))
    )
    (net (code "98") (name "unconnected-(U$1-AIO0-Pad30)") (class "Default")
      (node (ref "U$1") (pin "30") (pinfunction "AIO0_30") (pintype "bidirectional"))
    )
    (net (code "99") (name "unconnected-(U$1-AIO1-Pad35)") (class "Default")
      (node (ref "U$1") (pin "35") (pinfunction "AIO1_35") (pintype "bidirectional"))
    )
    (net (code "100") (name "unconnected-(U$1-PCMCLK-Pad7)") (class "Default")
      (node (ref "U$1") (pin "7") (pinfunction "PCMCLK_7") (pintype "bidirectional"))
    )
    (net (code "101") (name "unconnected-(U$1-PCMIN-Pad9)") (class "Default")
      (node (ref "U$1") (pin "9") (pinfunction "PCMIN_9") (pintype "bidirectional"))
    )
    (net (code "102") (name "unconnected-(U$1-PCMOUT-Pad10)") (class "Default")
      (node (ref "U$1") (pin "10") (pinfunction "PCMOUT_10") (pintype "bidirectional"))
    )
    (net (code "103") (name "unconnected-(U$1-PCMSYNC-Pad8)") (class "Default")
      (node (ref "U$1") (pin "8") (pinfunction "PCMSYNC_8") (pintype "bidirectional"))
    )
    (net (code "104") (name "unconnected-(U$1-PIO9-Pad32)") (class "Default")
      (node (ref "U$1") (pin "32") (pinfunction "PIO9_32") (pintype "bidirectional"))
    )
    (net (code "105") (name "unconnected-(U$1-PIO10-Pad33)") (class "Default")
      (node (ref "U$1") (pin "33") (pinfunction "PIO10_33") (pintype "bidirectional"))
    )
    (net (code "106") (name "unconnected-(U$1-PIO11-Pad34)") (class "Default")
      (node (ref "U$1") (pin "34") (pinfunction "PIO11_34") (pintype "bidirectional"))
    )
    (net (code "107") (name "unconnected-(U$1-SPICLK-Pad6)") (class "Default")
      (node (ref "U$1") (pin "6") (pinfunction "SPICLK_6") (pintype "bidirectional"))
    )
    (net (code "108") (name "unconnected-(U$1-SPICSB-Pad23)") (class "Default")
      (node (ref "U$1") (pin "23") (pinfunction "SPICSB_23") (pintype "bidirectional"))
    )
    (net (code "109") (name "unconnected-(U$1-SPIMISO-Pad24)") (class "Default")
      (node (ref "U$1") (pin "24") (pinfunction "SPIMISO_24") (pintype "bidirectional"))
    )
    (net (code "110") (name "unconnected-(U$1-SPIMOSI-Pad2)") (class "Default")
      (node (ref "U$1") (pin "2") (pinfunction "SPIMOSI_2") (pintype "bidirectional"))
    )
    (net (code "111") (name "unconnected-(U$1-USBD+-Pad17)") (class "Default")
      (node (ref "U$1") (pin "17") (pinfunction "USBD+_17") (pintype "bidirectional"))
    )
    (net (code "112") (name "unconnected-(U$1-USBD--Pad18)") (class "Default")
      (node (ref "U$1") (pin "18") (pinfunction "USBD-_18") (pintype "bidirectional"))
    )
  )
)
